# Sheet2.net
KiCad netlist of a schematic drawn in Altium Designer
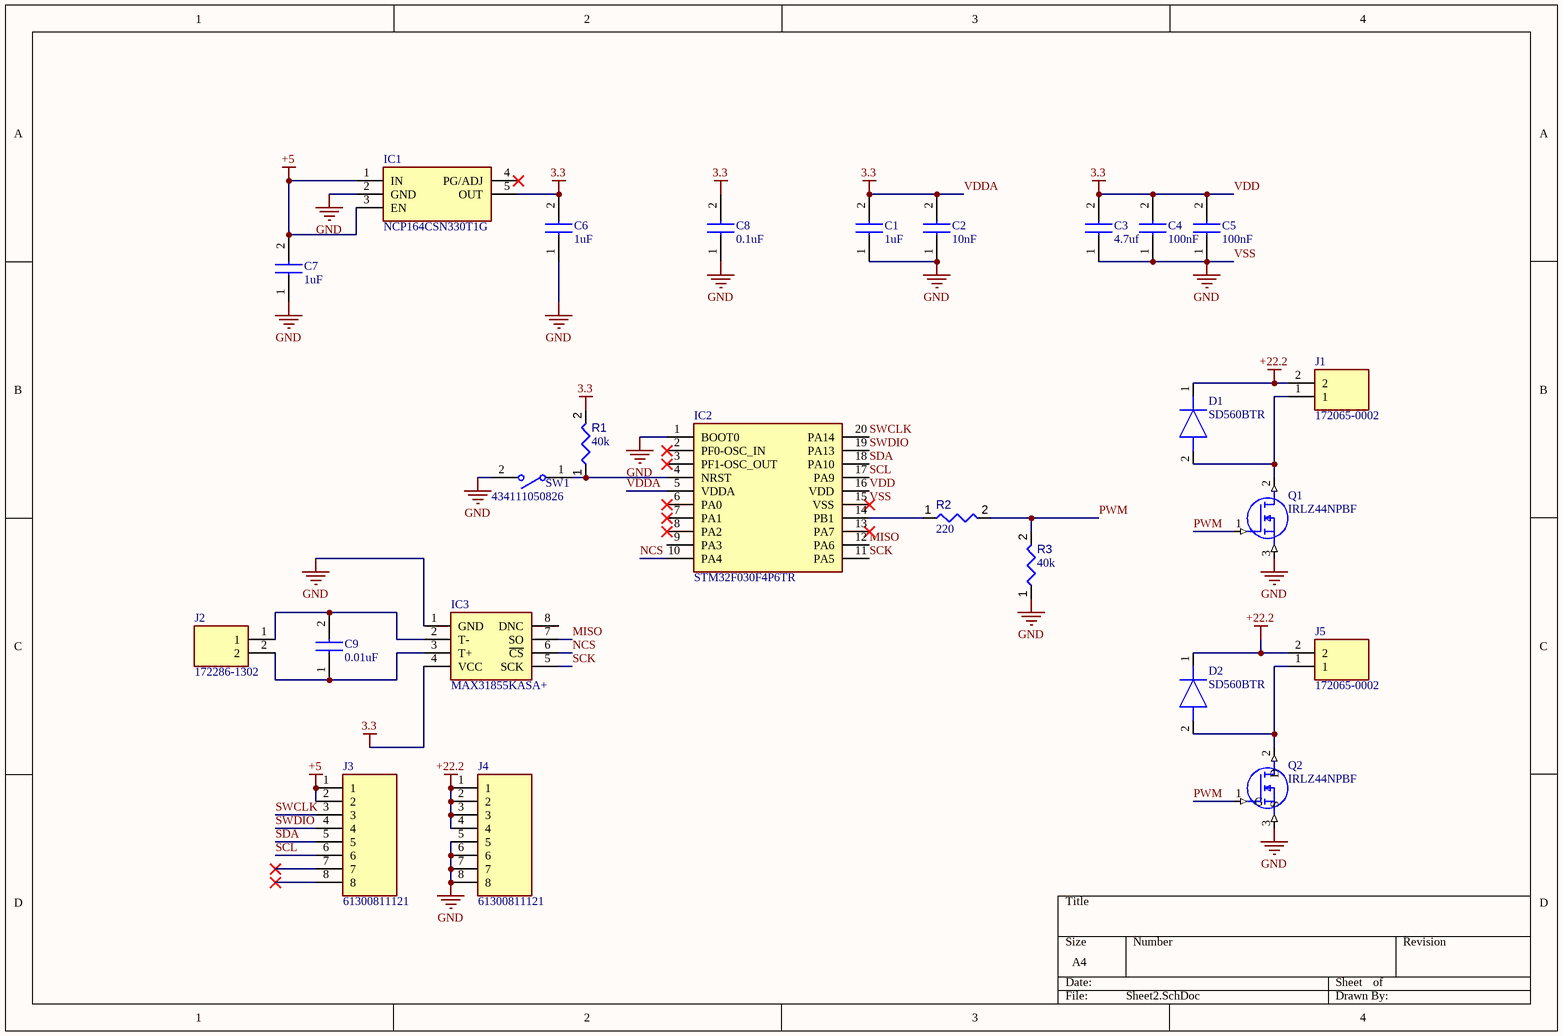
[diagram p0: Sheet2.SchDoc]

(export (version "E")
  (design (tool "Eeschema 10.0.6"))
  (components
    (comp (ref "C1")
      (value "1uF")
      (footprint "SamacSys:CAPC2012X94N")
      (description "Capacitor")
      (fields
        (field (name "MANUFACTURER_PART_NUMBER") "08055C104K4T2A")
        (field (name "MOUSER PART NUMBER") "581-08055C104K4")
      )
      (libsource (lib "*") (part "08055C104K4T2A"))
    )
    (comp (ref "C2")
      (value "10nF")
      (footprint "SamacSys:CAPC2012X94N")
      (description "Capacitor")
      (fields
        (field (name "MANUFACTURER_PART_NUMBER") "08055C104K4T2A")
        (field (name "MOUSER PART NUMBER") "581-08055C104K4")
      )
      (libsource (lib "*") (part "08055C104K4T2A"))
    )
    (comp (ref "C3")
      (value "4.7uf")
      (footprint "SamacSys:CAPC2012X94N")
      (description "Capacitor")
      (fields
        (field (name "MANUFACTURER_PART_NUMBER") "08055C104K4T2A")
        (field (name "MOUSER PART NUMBER") "581-08055C104K4")
      )
      (libsource (lib "*") (part "08055C104K4T2A"))
    )
    (comp (ref "C4")
      (value "100nF")
      (footprint "SamacSys:CAPC2012X94N")
      (description "Capacitor")
      (fields
        (field (name "MANUFACTURER_PART_NUMBER") "08055C104K4T2A")
        (field (name "MOUSER PART NUMBER") "581-08055C104K4")
      )
      (libsource (lib "*") (part "08055C104K4T2A"))
    )
    (comp (ref "C5")
      (value "100nF")
      (footprint "SamacSys:CAPC2012X94N")
      (description "Capacitor")
      (fields
        (field (name "MANUFACTURER_PART_NUMBER") "08055C104K4T2A")
        (field (name "MOUSER PART NUMBER") "581-08055C104K4")
      )
      (libsource (lib "*") (part "08055C104K4T2A"))
    )
    (comp (ref "C6")
      (value "1uF")
      (footprint "SamacSys:CAPC2012X94N")
      (description "Capacitor")
      (fields
        (field (name "MANUFACTURER_PART_NUMBER") "08055C104K4T2A")
        (field (name "MOUSER PART NUMBER") "581-08055C104K4")
      )
      (libsource (lib "*") (part "08055C104K4T2A"))
    )
    (comp (ref "C7")
      (value "1uF")
      (footprint "SamacSys:CAPC2012X94N")
      (description "Capacitor")
      (fields
        (field (name "MANUFACTURER_PART_NUMBER") "08055C104K4T2A")
        (field (name "MOUSER PART NUMBER") "581-08055C104K4")
      )
      (libsource (lib "*") (part "08055C104K4T2A"))
    )
    (comp (ref "C8")
      (value "0.1uF")
      (footprint "SamacSys:CAPC2012X94N")
      (description "Capacitor")
      (fields
        (field (name "MANUFACTURER_PART_NUMBER") "08055C104K4T2A")
        (field (name "MOUSER PART NUMBER") "581-08055C104K4")
      )
      (libsource (lib "*") (part "08055C104K4T2A"))
    )
    (comp (ref "C9")
      (value "0.01uF")
      (footprint "SamacSys:CAPC2012X94N")
      (description "Capacitor")
      (fields
        (field (name "MANUFACTURER_PART_NUMBER") "08055C104K4T2A")
        (field (name "MOUSER PART NUMBER") "581-08055C104K4")
      )
      (libsource (lib "*") (part "08055C104K4T2A"))
    )
    (comp (ref "D1")
      (value "SD560BTR")
      (footprint "SamacSys:DIOM5236X260N")
      (description "Diode")
      (libsource (lib "*") (part "SD560BTR"))
    )
    (comp (ref "D2")
      (value "SD560BTR")
      (footprint "SamacSys:DIOM5236X260N")
      (description "Diode")
      (libsource (lib "*") (part "SD560BTR"))
    )
    (comp (ref "IC1")
      (value "NCP164CSN330T1G")
      (footprint "SamacSys:SOT95P275X110-5N")
      (description "Integrated Circuit")
      (fields (field (name "MOUSER PART NUMBER") "863-NCP164CSN330T1G"))
      (libsource (lib "*") (part "NCP164CSN330T1G"))
    )
    (comp (ref "IC2")
      (value "STM32F030F4P6TR")
      (footprint "SamacSys:SOP65P640X120-20N")
      (description "Integrated Circuit")
      (fields (field (name "MOUSER PART NUMBER") "511-STM32F030F4P6TR"))
      (libsource (lib "*") (part "STM32F030F4P6TR"))
    )
    (comp (ref "IC3")
      (value "MAX31855KASA+")
      (footprint "SamacSys:SOIC127P600X175-8N")
      (description "Integrated Circuit")
      (fields (field (name "MOUSER PART NUMBER") "700-MAX31855KASA+"))
      (libsource (lib "*") (part "MAX31855KASA+"))
    )
    (comp (ref "J1")
      (value "172065-0002")
      (footprint "SamacSys:1720650002")
      (description "Connector")
      (fields (field (name "MOUSER PART NUMBER") "538-172065-0002"))
      (libsource (lib "*") (part "172065-0002"))
    )
    (comp (ref "J2")
      (value "172286-1302")
      (footprint "SamacSys:172286-YY02")
      (description "Connector")
      (fields (field (name "MOUSER PART NUMBER") "538-172286-1302"))
      (libsource (lib "*") (part "172286-1302"))
    )
    (comp (ref "J3")
      (value "61300811121")
      (footprint "SamacSys:HDRV8W64P0X254_1X8_2032X254X854P")
      (description "Connector")
      (fields (field (name "MOUSER PART NUMBER") "710-61300811121"))
      (libsource (lib "*") (part "61300811121"))
    )
    (comp (ref "J4")
      (value "61300811121")
      (footprint "SamacSys:HDRV8W64P0X254_1X8_2032X254X854P")
      (description "Connector")
      (fields (field (name "MOUSER PART NUMBER") "710-61300811121"))
      (libsource (lib "*") (part "61300811121"))
    )
    (comp (ref "J5")
      (value "172065-0002")
      (footprint "SamacSys:1720650002")
      (description "Connector")
      (fields (field (name "MOUSER PART NUMBER") "538-172065-0002"))
      (libsource (lib "*") (part "172065-0002"))
    )
    (comp (ref "Q1")
      (value "IRLZ44NPBF")
      (footprint "SamacSys:TO254P469X1042X1967-3P")
      (description "MOSFET (N-Channel)")
      (fields (field (name "MOUSER PART NUMBER") "942-IRLZ44NPBF"))
      (libsource (lib "") (part "IRLZ44NPBF_1"))
    )
    (comp (ref "Q2")
      (value "IRLZ44NPBF")
      (footprint "SamacSys:TO254P469X1042X1967-3P")
      (description "MOSFET (N-Channel)")
      (fields (field (name "MOUSER PART NUMBER") "942-IRLZ44NPBF"))
      (libsource (lib "*") (part "IRLZ44NPBF"))
    )
    (comp (ref "R1")
      (value "40k")
      (footprint "RESC0805(2012)_L")
      (description "Chip Resistor, 4,7 Ohms, +/-5 %, 125 mW, -55 to 155 degC, 0805")
      (fields (field (name "TOLERANCE") "5%") (field (name "POWER") "125mW"))
      (libsource (lib "CPRT Workspace") (part "RES-2"))
    )
    (comp (ref "R2")
      (value "220")
      (footprint "RESC0805(2012)_L")
      (description "Chip Resistor, 4,7 Ohms, +/-5 %, 125 mW, -55 to 155 degC, 0805")
      (fields (field (name "TOLERANCE") "5%") (field (name "POWER") "125mW"))
      (libsource (lib "CPRT Workspace") (part "RES-2"))
    )
    (comp (ref "R3")
      (value "40k")
      (footprint "RESC0805(2012)_L")
      (description "Chip Resistor, 4,7 Ohms, +/-5 %, 125 mW, -55 to 155 degC, 0805")
      (fields (field (name "TOLERANCE") "5%") (field (name "POWER") "125mW"))
      (libsource (lib "CPRT Workspace") (part "RES-2"))
    )
    (comp (ref "SW1")
      (value "434111050826")
      (footprint "434111050826")
      (libsource (lib "CPRT Workspace") (part "SPST-NO_2P"))
    )
  )
  (nets
    (net (code "1") (name "+5") (class "Default")
      (node (ref "C7") (pin "2") (pinfunction "2_2") (pintype "passive"))
      (node (ref "IC1") (pin "1") (pinfunction "IN_1") (pintype "passive"))
      (node (ref "IC1") (pin "3") (pinfunction "EN_3") (pintype "passive"))
      (node (ref "J3") (pin "1") (pinfunction "1_1") (pintype "passive"))
      (node (ref "J3") (pin "2") (pinfunction "2_2") (pintype "passive"))
    )
    (net (code "2") (name "+22.2") (class "Default")
      (node (ref "D1") (pin "1") (pinfunction "K_1") (pintype "passive"))
      (node (ref "D2") (pin "1") (pinfunction "K_1") (pintype "passive"))
      (node (ref "J1") (pin "2") (pinfunction "2_2") (pintype "passive"))
      (node (ref "J4") (pin "1") (pinfunction "1_1") (pintype "passive"))
      (node (ref "J4") (pin "2") (pinfunction "2_2") (pintype "passive"))
      (node (ref "J4") (pin "3") (pinfunction "3_3") (pintype "passive"))
      (node (ref "J4") (pin "4") (pinfunction "4_4") (pintype "passive"))
      (node (ref "J5") (pin "2") (pinfunction "2_2") (pintype "passive"))
    )
    (net (code "3") (name "/MISO") (class "Default")
      (node (ref "IC2") (pin "12") (pinfunction "PA6_12") (pintype "passive"))
      (node (ref "IC3") (pin "7") (pinfunction "SO_7") (pintype "passive"))
    )
    (net (code "4") (name "/NCS") (class "Default")
      (node (ref "IC2") (pin "10") (pinfunction "PA4_10") (pintype "passive"))
      (node (ref "IC3") (pin "6") (pinfunction "~{CS}_6") (pintype "passive"))
    )
    (net (code "5") (name "/PWM") (class "Default")
      (node (ref "Q1") (pin "1") (pinfunction "G_1") (pintype "input"))
      (node (ref "Q2") (pin "1") (pinfunction "G_1") (pintype "input"))
      (node (ref "R2") (pin "2") (pinfunction "2_2") (pintype "passive"))
      (node (ref "R3") (pin "2") (pinfunction "2_2") (pintype "passive"))
    )
    (net (code "6") (name "/SCK") (class "Default")
      (node (ref "IC2") (pin "11") (pinfunction "PA5_11") (pintype "passive"))
      (node (ref "IC3") (pin "5") (pinfunction "SCK_5") (pintype "passive"))
    )
    (net (code "7") (name "/SCL") (class "Default")
      (node (ref "IC2") (pin "17") (pinfunction "PA9_17") (pintype "passive"))
      (node (ref "J3") (pin "6") (pinfunction "6_6") (pintype "passive"))
    )
    (net (code "8") (name "/SDA") (class "Default")
      (node (ref "IC2") (pin "18") (pinfunction "PA10_18") (pintype "passive"))
      (node (ref "J3") (pin "5") (pinfunction "5_5") (pintype "passive"))
    )
    (net (code "9") (name "/SWCLK") (class "Default")
      (node (ref "IC2") (pin "20") (pinfunction "PA14_20") (pintype "passive"))
      (node (ref "J3") (pin "3") (pinfunction "3_3") (pintype "passive"))
    )
    (net (code "10") (name "/SWDIO") (class "Default")
      (node (ref "IC2") (pin "19") (pinfunction "PA13_19") (pintype "passive"))
      (node (ref "J3") (pin "4") (pinfunction "4_4") (pintype "passive"))
    )
    (net (code "11") (name "3.3") (class "Default")
      (node (ref "C1") (pin "2") (pinfunction "2_2") (pintype "passive"))
      (node (ref "C2") (pin "2") (pinfunction "2_2") (pintype "passive"))
      (node (ref "C3") (pin "2") (pinfunction "2_2") (pintype "passive"))
      (node (ref "C4") (pin "2") (pinfunction "2_2") (pintype "passive"))
      (node (ref "C5") (pin "2") (pinfunction "2_2") (pintype "passive"))
      (node (ref "C6") (pin "2") (pinfunction "2_2") (pintype "passive"))
      (node (ref "C8") (pin "2") (pinfunction "2_2") (pintype "passive"))
      (node (ref "IC1") (pin "5") (pinfunction "OUT_5") (pintype "passive"))
      (node (ref "IC2") (pin "16") (pinfunction "VDD_16") (pintype "passive"))
      (node (ref "IC2") (pin "5") (pinfunction "VDDA_5") (pintype "passive"))
      (node (ref "IC3") (pin "4") (pinfunction "VCC_4") (pintype "passive"))
      (node (ref "R1") (pin "2") (pinfunction "2_2") (pintype "passive"))
    )
    (net (code "12") (name "GND") (class "Default")
      (node (ref "C1") (pin "1") (pinfunction "1_1") (pintype "passive"))
      (node (ref "C2") (pin "1") (pinfunction "1_1") (pintype "passive"))
      (node (ref "C3") (pin "1") (pinfunction "1_1") (pintype "passive"))
      (node (ref "C4") (pin "1") (pinfunction "1_1") (pintype "passive"))
      (node (ref "C5") (pin "1") (pinfunction "1_1") (pintype "passive"))
      (node (ref "C6") (pin "1") (pinfunction "1_1") (pintype "passive"))
      (node (ref "C7") (pin "1") (pinfunction "1_1") (pintype "passive"))
      (node (ref "C8") (pin "1") (pinfunction "1_1") (pintype "passive"))
      (node (ref "IC1") (pin "2") (pinfunction "GND_2") (pintype "passive"))
      (node (ref "IC2") (pin "1") (pinfunction "BOOT0_1") (pintype "passive"))
      (node (ref "IC2") (pin "15") (pinfunction "VSS_15") (pintype "passive"))
      (node (ref "IC3") (pin "1") (pinfunction "GND_1") (pintype "passive"))
      (node (ref "J4") (pin "5") (pinfunction "5_5") (pintype "passive"))
      (node (ref "J4") (pin "6") (pinfunction "6_6") (pintype "passive"))
      (node (ref "J4") (pin "7") (pinfunction "7_7") (pintype "passive"))
      (node (ref "J4") (pin "8") (pinfunction "8_8") (pintype "passive"))
      (node (ref "Q1") (pin "3") (pinfunction "S_3") (pintype "input"))
      (node (ref "Q2") (pin "3") (pinfunction "S_3") (pintype "input"))
      (node (ref "R3") (pin "1") (pinfunction "1_1") (pintype "passive"))
      (node (ref "SW1") (pin "2") (pinfunction "2_2") (pintype "passive"))
    )
    (net (code "13") (name "Net-(D1-A)") (class "Default")
      (node (ref "D1") (pin "2") (pinfunction "A_2") (pintype "passive"))
      (node (ref "J1") (pin "1") (pinfunction "1_1") (pintype "passive"))
      (node (ref "Q1") (pin "2") (pinfunction "D_2") (pintype "output"))
    )
    (net (code "14") (name "Net-(D2-A)") (class "Default")
      (node (ref "D2") (pin "2") (pinfunction "A_2") (pintype "passive"))
      (node (ref "J5") (pin "1") (pinfunction "1_1") (pintype "passive"))
      (node (ref "Q2") (pin "2") (pinfunction "D_2") (pintype "output"))
    )
    (net (code "15") (name "Net-(IC2-NRST)") (class "Default")
      (node (ref "IC2") (pin "4") (pinfunction "NRST_4") (pintype "passive"))
      (node (ref "R1") (pin "1") (pinfunction "1_1") (pintype "passive"))
      (node (ref "SW1") (pin "1") (pinfunction "1_1") (pintype "passive"))
    )
    (net (code "16") (name "Net-(IC2-PB1)") (class "Default")
      (node (ref "IC2") (pin "14") (pinfunction "PB1_14") (pintype "passive"))
      (node (ref "R2") (pin "1") (pinfunction "1_1") (pintype "passive"))
    )
    (net (code "17") (name "Net-(IC3-T+)") (class "Default")
      (node (ref "C9") (pin "1") (pinfunction "1_1") (pintype "passive"))
      (node (ref "IC3") (pin "3") (pinfunction "T+_3") (pintype "passive"))
      (node (ref "J2") (pin "2") (pinfunction "2_2") (pintype "passive"))
    )
    (net (code "18") (name "Net-(IC3-T-)") (class "Default")
      (node (ref "C9") (pin "2") (pinfunction "2_2") (pintype "passive"))
      (node (ref "IC3") (pin "2") (pinfunction "T-_2") (pintype "passive"))
      (node (ref "J2") (pin "1") (pinfunction "1_1") (pintype "passive"))
    )
    (net (code "19") (name "unconnected-(IC1-PG{slash}ADJ-Pad4)") (class "Default")
      (node (ref "IC1") (pin "4") (pinfunction "PG/ADJ_4") (pintype "passive+no_connect"))
    )
    (net (code "20") (name "unconnected-(IC2-PA0-Pad6)") (class "Default")
      (node (ref "IC2") (pin "6") (pinfunction "PA0_6") (pintype "passive+no_connect"))
    )
    (net (code "21") (name "unconnected-(IC2-PA1-Pad7)") (class "Default")
      (node (ref "IC2") (pin "7") (pinfunction "PA1_7") (pintype "passive+no_connect"))
    )
    (net (code "22") (name "unconnected-(IC2-PA2-Pad8)") (class "Default")
      (node (ref "IC2") (pin "8") (pinfunction "PA2_8") (pintype "passive+no_connect"))
    )
    (net (code "23") (name "unconnected-(IC2-PA3-Pad9)") (class "Default")
      (node (ref "IC2") (pin "9") (pinfunction "PA3_9") (pintype "passive"))
    )
    (net (code "24") (name "unconnected-(IC2-PA7-Pad13)") (class "Default")
      (node (ref "IC2") (pin "13") (pinfunction "PA7_13") (pintype "passive+no_connect"))
    )
    (net (code "25") (name "unconnected-(IC2-PF0-OSC_IN-Pad2)") (class "Default")
      (node (ref "IC2") (pin "2") (pinfunction "PF0-OSC_IN_2") (pintype "passive+no_connect"))
    )
    (net (code "26") (name "unconnected-(IC2-PF1-OSC_OUT-Pad3)") (class "Default")
      (node (ref "IC2") (pin "3") (pinfunction "PF1-OSC_OUT_3") (pintype "passive+no_connect"))
    )
    (net (code "27") (name "unconnected-(IC3-DNC-Pad8)") (class "Default")
      (node (ref "IC3") (pin "8") (pinfunction "DNC_8") (pintype "passive"))
    )
    (net (code "28") (name "unconnected-(J3-Pad7)") (class "Default")
      (node (ref "J3") (pin "7") (pinfunction "7_7") (pintype "passive+no_connect"))
    )
    (net (code "29") (name "unconnected-(J3-Pad8)") (class "Default")
      (node (ref "J3") (pin "8") (pinfunction "8_8") (pintype "passive+no_connect"))
    )
  )
)
